# dualAudio2Gate.net
KiCad netlist of a schematic drawn in EAGLE
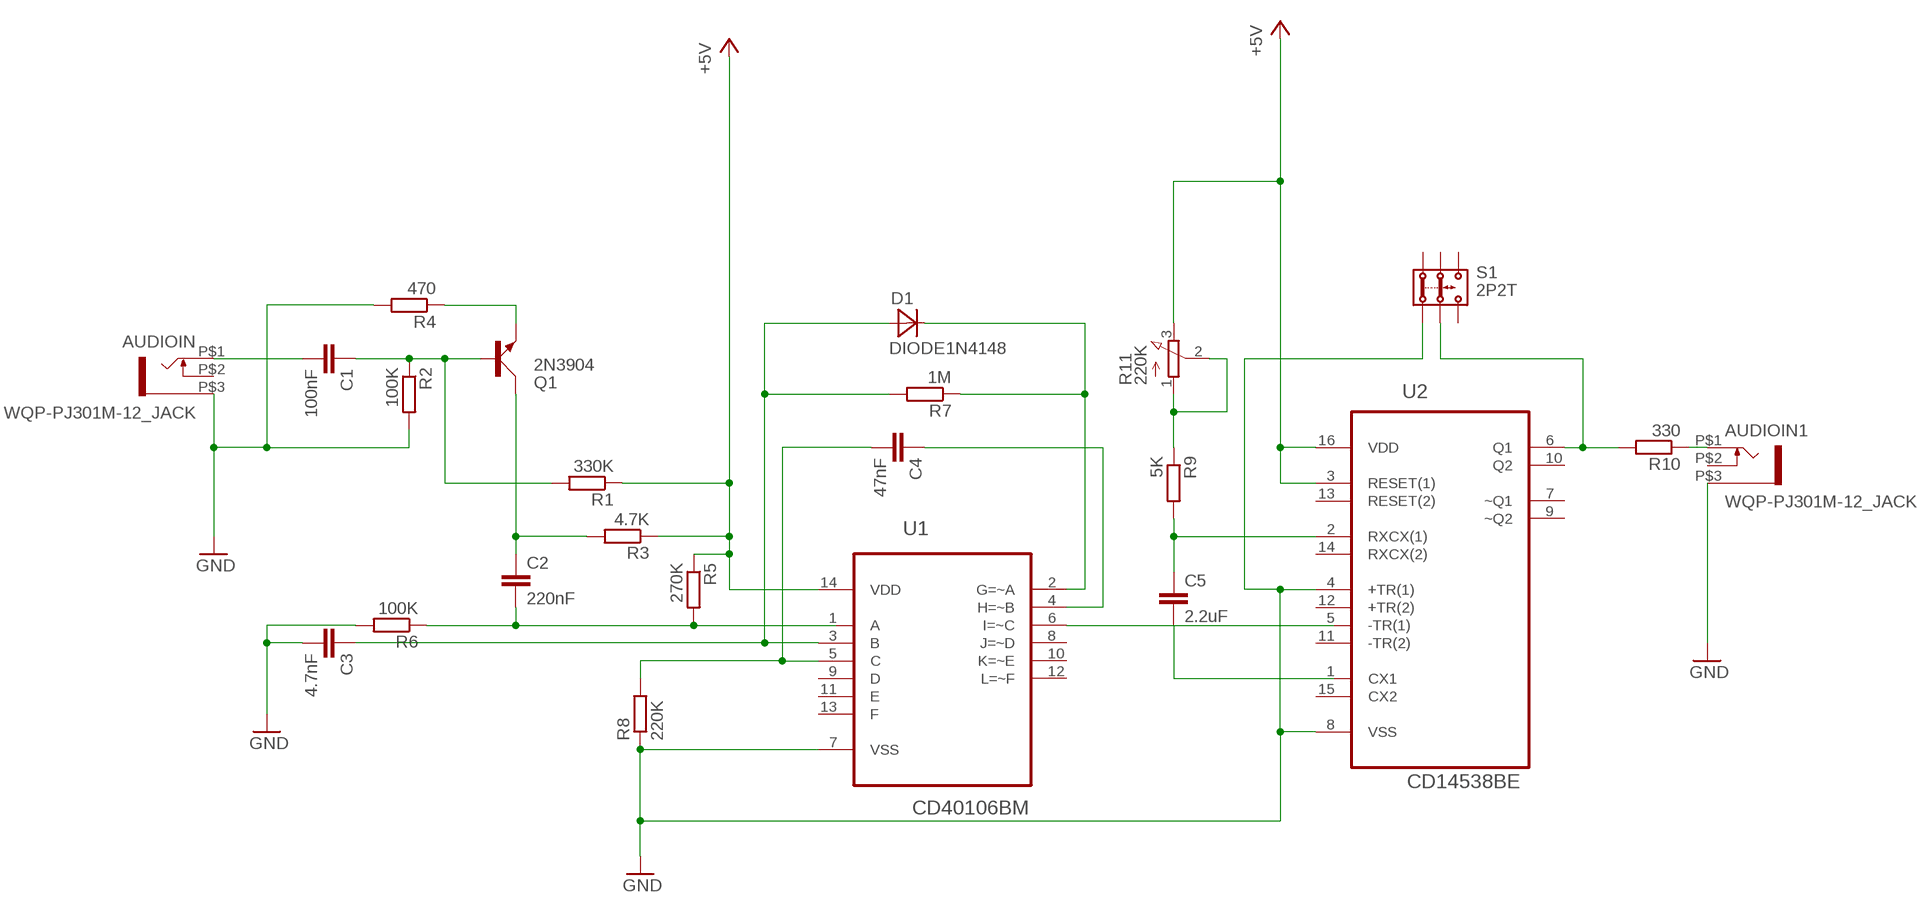
[diagram p0: schematic, sheet 1]

(export (version "E")
  (design (tool "Eeschema 10.0.6"))
  (components
    (comp (ref "AUDIOIN")
      (value "WQP-PJ301M-12_JACK")
      (footprint "eagle-import:WQP-PJ301M-12_JACK")
      (libsource (lib "eagle-import") (part "WQP-PJ301M-12_JACK"))
    )
    (comp (ref "AUDIOIN1")
      (value "WQP-PJ301M-12_JACK")
      (footprint "eagle-import:WQP-PJ301M-12_JACK")
      (libsource (lib "eagle-import") (part "WQP-PJ301M-12_JACK"))
    )
    (comp (ref "C1")
      (value "100nF")
      (footprint "eagle-import:C025-025X050")
      (libsource (lib "eagle-import") (part "C-EU025-025X050"))
    )
    (comp (ref "C2")
      (value "220nF")
      (footprint "eagle-import:C025-025X050")
      (libsource (lib "eagle-import") (part "C-EU025-025X050"))
    )
    (comp (ref "C3")
      (value "4.7nF")
      (footprint "eagle-import:C025-025X050")
      (libsource (lib "eagle-import") (part "C-EU025-025X050"))
    )
    (comp (ref "C4")
      (value "47nF")
      (footprint "eagle-import:C025-025X050")
      (libsource (lib "eagle-import") (part "C-EU025-025X050"))
    )
    (comp (ref "C5")
      (value "2.2uF")
      (footprint "eagle-import:C025-025X050")
      (libsource (lib "eagle-import") (part "C-EU025-025X050"))
    )
    (comp (ref "D1")
      (value "DIODE1N4148")
      (footprint "eagle-import:DO-35")
      (libsource (lib "eagle-import") (part "DIODE1N4148"))
    )
    (comp (ref "Q1")
      (value "2N3904")
      (footprint "eagle-import:TO92D")
      (libsource (lib "eagle-import") (part "2N3904"))
    )
    (comp (ref "R1")
      (value "330K")
      (footprint "eagle-import:0204V")
      (libsource (lib "eagle-import") (part "R-EU_0204/2V"))
    )
    (comp (ref "R2")
      (value "100K")
      (footprint "eagle-import:0204V")
      (libsource (lib "eagle-import") (part "R-EU_0204/2V"))
    )
    (comp (ref "R3")
      (value "4.7K")
      (footprint "eagle-import:0204V")
      (libsource (lib "eagle-import") (part "R-EU_0204/2V"))
    )
    (comp (ref "R4")
      (value "470")
      (footprint "eagle-import:0204V")
      (libsource (lib "eagle-import") (part "R-EU_0204/2V"))
    )
    (comp (ref "R5")
      (value "270K")
      (footprint "eagle-import:0204V")
      (libsource (lib "eagle-import") (part "R-EU_0204/2V"))
    )
    (comp (ref "R6")
      (value "100K")
      (footprint "eagle-import:0204V")
      (libsource (lib "eagle-import") (part "R-EU_0204/2V"))
    )
    (comp (ref "R7")
      (value "1M")
      (footprint "eagle-import:0204V")
      (libsource (lib "eagle-import") (part "R-EU_0204/2V"))
    )
    (comp (ref "R8")
      (value "220K")
      (footprint "eagle-import:0204V")
      (libsource (lib "eagle-import") (part "R-EU_0204/2V"))
    )
    (comp (ref "R9")
      (value "5K")
      (footprint "eagle-import:0204V")
      (libsource (lib "eagle-import") (part "R-EU_0204/2V"))
    )
    (comp (ref "R10")
      (value "330")
      (footprint "eagle-import:0204V")
      (libsource (lib "eagle-import") (part "R-EU_0204/2V"))
    )
    (comp (ref "R11")
      (value "220K")
      (footprint "eagle-import:3RP_1610N")
      (libsource (lib "eagle-import") (part "3RP/1610N"))
    )
    (comp (ref "S1")
      (value "2P2T")
      (footprint "eagle-import:2P2T")
      (libsource (lib "eagle-import") (part "2P2T"))
    )
    (comp (ref "U1")
      (value "CD40106BM")
      (footprint "eagle-import:SOIC127P600X175-14N")
      (libsource (lib "eagle-import") (part "CD40106BM"))
    )
    (comp (ref "U2")
      (value "CD14538BE")
      (footprint "eagle-import:DIP254P762X508-16")
      (libsource (lib "eagle-import") (part "CD14538BE"))
    )
  )
  (nets
    (net (code "1") (name "+5V") (class "Default")
      (node (ref "R1") (pin "1") (pinfunction "1_1") (pintype "passive"))
      (node (ref "R11") (pin "3") (pinfunction "E_3") (pintype "passive"))
      (node (ref "R3") (pin "1") (pinfunction "1_1") (pintype "passive"))
      (node (ref "R5") (pin "1") (pinfunction "1_1") (pintype "passive"))
      (node (ref "U1") (pin "14") (pinfunction "VDD_14") (pintype "power_in"))
      (node (ref "U2") (pin "16") (pinfunction "VDD_16") (pintype "power_in"))
      (node (ref "U2") (pin "3") (pinfunction "RESET(1)_3") (pintype "input"))
    )
    (net (code "2") (name "GND") (class "Default")
      (node (ref "AUDIOIN") (pin "P$3") (pinfunction "1_P$3") (pintype "passive"))
      (node (ref "AUDIOIN1") (pin "P$3") (pinfunction "1_P$3") (pintype "passive"))
      (node (ref "C3") (pin "2") (pinfunction "2_2") (pintype "passive"))
      (node (ref "R2") (pin "2") (pinfunction "2_2") (pintype "passive"))
      (node (ref "R4") (pin "2") (pinfunction "2_2") (pintype "passive"))
      (node (ref "R6") (pin "2") (pinfunction "2_2") (pintype "passive"))
      (node (ref "R8") (pin "1") (pinfunction "1_1") (pintype "passive"))
      (node (ref "S1") (pin "1.2") (pinfunction "1.2_1.2") (pintype "passive"))
      (node (ref "U1") (pin "7") (pinfunction "VSS_7") (pintype "power_in"))
      (node (ref "U2") (pin "4") (pinfunction "+TR(1)_4") (pintype "input"))
      (node (ref "U2") (pin "8") (pinfunction "VSS_8") (pintype "power_in"))
    )
    (net (code "3") (name "Net-(AUDIOIN-2)") (class "Default")
      (node (ref "AUDIOIN") (pin "P$1") (pinfunction "2_P$1") (pintype "passive"))
      (node (ref "C1") (pin "2") (pinfunction "2_2") (pintype "passive"))
    )
    (net (code "4") (name "Net-(AUDIOIN1-2)") (class "Default")
      (node (ref "AUDIOIN1") (pin "P$1") (pinfunction "2_P$1") (pintype "passive"))
      (node (ref "R10") (pin "1") (pinfunction "1_1") (pintype "passive"))
    )
    (net (code "5") (name "Net-(C1-Pad1)") (class "Default")
      (node (ref "C1") (pin "1") (pinfunction "1_1") (pintype "passive"))
      (node (ref "Q1") (pin "B") (pinfunction "B_B") (pintype "passive"))
      (node (ref "R1") (pin "2") (pinfunction "2_2") (pintype "passive"))
      (node (ref "R2") (pin "1") (pinfunction "1_1") (pintype "passive"))
    )
    (net (code "6") (name "Net-(C2-Pad1)") (class "Default")
      (node (ref "C2") (pin "1") (pinfunction "1_1") (pintype "passive"))
      (node (ref "Q1") (pin "C") (pinfunction "C_C") (pintype "passive"))
      (node (ref "R3") (pin "2") (pinfunction "2_2") (pintype "passive"))
    )
    (net (code "7") (name "Net-(C2-Pad2)") (class "Default")
      (node (ref "C2") (pin "2") (pinfunction "2_2") (pintype "passive"))
      (node (ref "R5") (pin "2") (pinfunction "2_2") (pintype "passive"))
      (node (ref "R6") (pin "1") (pinfunction "1_1") (pintype "passive"))
    )
    (net (code "8") (name "Net-(Q1-PadE)") (class "Default")
      (node (ref "Q1") (pin "E") (pinfunction "E_E") (pintype "passive"))
      (node (ref "R4") (pin "1") (pinfunction "1_1") (pintype "passive"))
    )
    (net (code "9") (name "Net-(R11-A)") (class "Default")
      (node (ref "R11") (pin "1") (pinfunction "A_1") (pintype "passive"))
      (node (ref "R11") (pin "2") (pinfunction "S_2") (pintype "passive"))
      (node (ref "R9") (pin "1") (pinfunction "1_1") (pintype "passive"))
    )
    (net (code "10") (name "Net-(U1-B)") (class "Default")
      (node (ref "C3") (pin "1") (pinfunction "1_1") (pintype "passive"))
      (node (ref "D1") (pin "+") (pinfunction "+_+") (pintype "passive"))
      (node (ref "R7") (pin "2") (pinfunction "2_2") (pintype "passive"))
      (node (ref "U1") (pin "3") (pinfunction "B_3") (pintype "input"))
    )
    (net (code "11") (name "Net-(U1-C)") (class "Default")
      (node (ref "C4") (pin "2") (pinfunction "2_2") (pintype "passive"))
      (node (ref "R8") (pin "2") (pinfunction "2_2") (pintype "passive"))
      (node (ref "U1") (pin "5") (pinfunction "C_5") (pintype "input"))
    )
    (net (code "12") (name "Net-(U1-G=~{A})") (class "Default")
      (node (ref "D1") (pin "-") (pinfunction "-_-") (pintype "passive"))
      (node (ref "R7") (pin "1") (pinfunction "1_1") (pintype "passive"))
      (node (ref "U1") (pin "2") (pinfunction "G=~{A}_2") (pintype "output"))
    )
    (net (code "13") (name "Net-(U1-H=~{B})") (class "Default")
      (node (ref "C4") (pin "1") (pinfunction "1_1") (pintype "passive"))
      (node (ref "U1") (pin "4") (pinfunction "H=~{B}_4") (pintype "output"))
    )
    (net (code "14") (name "Net-(U1-I=~{C})") (class "Default")
      (node (ref "U1") (pin "6") (pinfunction "I=~{C}_6") (pintype "output"))
      (node (ref "U2") (pin "5") (pinfunction "-TR(1)_5") (pintype "input"))
    )
    (net (code "15") (name "Net-(U2-CX1)") (class "Default")
      (node (ref "C5") (pin "2") (pinfunction "2_2") (pintype "passive"))
      (node (ref "U2") (pin "1") (pinfunction "CX1_1") (pintype "input"))
    )
    (net (code "16") (name "Net-(U2-Q1)") (class "Default")
      (node (ref "R10") (pin "2") (pinfunction "2_2") (pintype "passive"))
      (node (ref "S1") (pin "2.2") (pinfunction "2.2_2.2") (pintype "passive"))
      (node (ref "U2") (pin "6") (pinfunction "Q1_6") (pintype "output"))
    )
    (net (code "17") (name "Net-(U2-RXCX(1))") (class "Default")
      (node (ref "C5") (pin "1") (pinfunction "1_1") (pintype "passive"))
      (node (ref "R9") (pin "2") (pinfunction "2_2") (pintype "passive"))
      (node (ref "U2") (pin "2") (pinfunction "RXCX(1)_2") (pintype "input"))
    )
    (net (code "18") (name "unconnected-(AUDIOIN-3-PadP$2)") (class "Default")
      (node (ref "AUDIOIN") (pin "P$2") (pinfunction "3_P$2") (pintype "passive"))
    )
    (net (code "19") (name "unconnected-(AUDIOIN1-3-PadP$2)") (class "Default")
      (node (ref "AUDIOIN1") (pin "P$2") (pinfunction "3_P$2") (pintype "passive"))
    )
    (net (code "20") (name "unconnected-(S1-Pad1.1)") (class "Default")
      (node (ref "S1") (pin "1.1") (pinfunction "1.1_1.1") (pintype "passive"))
    )
    (net (code "21") (name "unconnected-(S1-Pad2.1)") (class "Default")
      (node (ref "S1") (pin "2.1") (pinfunction "2.1_2.1") (pintype "passive"))
    )
    (net (code "22") (name "unconnected-(S1-Pad3.1)") (class "Default")
      (node (ref "S1") (pin "3.1") (pinfunction "3.1_3.1") (pintype "passive"))
    )
    (net (code "23") (name "unconnected-(S1-Pad3.2)") (class "Default")
      (node (ref "S1") (pin "3.2") (pinfunction "3.2_3.2") (pintype "passive"))
    )
    (net (code "24") (name "unconnected-(U1-A-Pad1)") (class "Default")
      (node (ref "U1") (pin "1") (pinfunction "A_1") (pintype "input"))
    )
    (net (code "25") (name "unconnected-(U1-D-Pad9)") (class "Default")
      (node (ref "U1") (pin "9") (pinfunction "D_9") (pintype "input"))
    )
    (net (code "26") (name "unconnected-(U1-E-Pad11)") (class "Default")
      (node (ref "U1") (pin "11") (pinfunction "E_11") (pintype "input"))
    )
    (net (code "27") (name "unconnected-(U1-F-Pad13)") (class "Default")
      (node (ref "U1") (pin "13") (pinfunction "F_13") (pintype "input"))
    )
    (net (code "28") (name "unconnected-(U1-J=~{D}-Pad8)") (class "Default")
      (node (ref "U1") (pin "8") (pinfunction "J=~{D}_8") (pintype "output"))
    )
    (net (code "29") (name "unconnected-(U1-K=~{E}-Pad10)") (class "Default")
      (node (ref "U1") (pin "10") (pinfunction "K=~{E}_10") (pintype "output"))
    )
    (net (code "30") (name "unconnected-(U1-L=~{F}-Pad12)") (class "Default")
      (node (ref "U1") (pin "12") (pinfunction "L=~{F}_12") (pintype "output"))
    )
    (net (code "31") (name "unconnected-(U2-+TR(2)-Pad12)") (class "Default")
      (node (ref "U2") (pin "12") (pinfunction "+TR(2)_12") (pintype "input"))
    )
    (net (code "32") (name "unconnected-(U2--TR(2)-Pad11)") (class "Default")
      (node (ref "U2") (pin "11") (pinfunction "-TR(2)_11") (pintype "input"))
    )
    (net (code "33") (name "unconnected-(U2-CX2-Pad15)") (class "Default")
      (node (ref "U2") (pin "15") (pinfunction "CX2_15") (pintype "input"))
    )
    (net (code "34") (name "unconnected-(U2-Q2-Pad10)") (class "Default")
      (node (ref "U2") (pin "10") (pinfunction "Q2_10") (pintype "output"))
    )
    (net (code "35") (name "unconnected-(U2-RESET(2)-Pad13)") (class "Default")
      (node (ref "U2") (pin "13") (pinfunction "RESET(2)_13") (pintype "input"))
    )
    (net (code "36") (name "unconnected-(U2-RXCX(2)-Pad14)") (class "Default")
      (node (ref "U2") (pin "14") (pinfunction "RXCX(2)_14") (pintype "input"))
    )
    (net (code "37") (name "unconnected-(U2-~{Q1}-Pad7)") (class "Default")
      (node (ref "U2") (pin "7") (pinfunction "~{Q1}_7") (pintype "output"))
    )
    (net (code "38") (name "unconnected-(U2-~{Q2}-Pad9)") (class "Default")
      (node (ref "U2") (pin "9") (pinfunction "~{Q2}_9") (pintype "output"))
    )
  )
)
